# E03_DAQ.net
KiCad netlist of a schematic drawn in Altium Designer
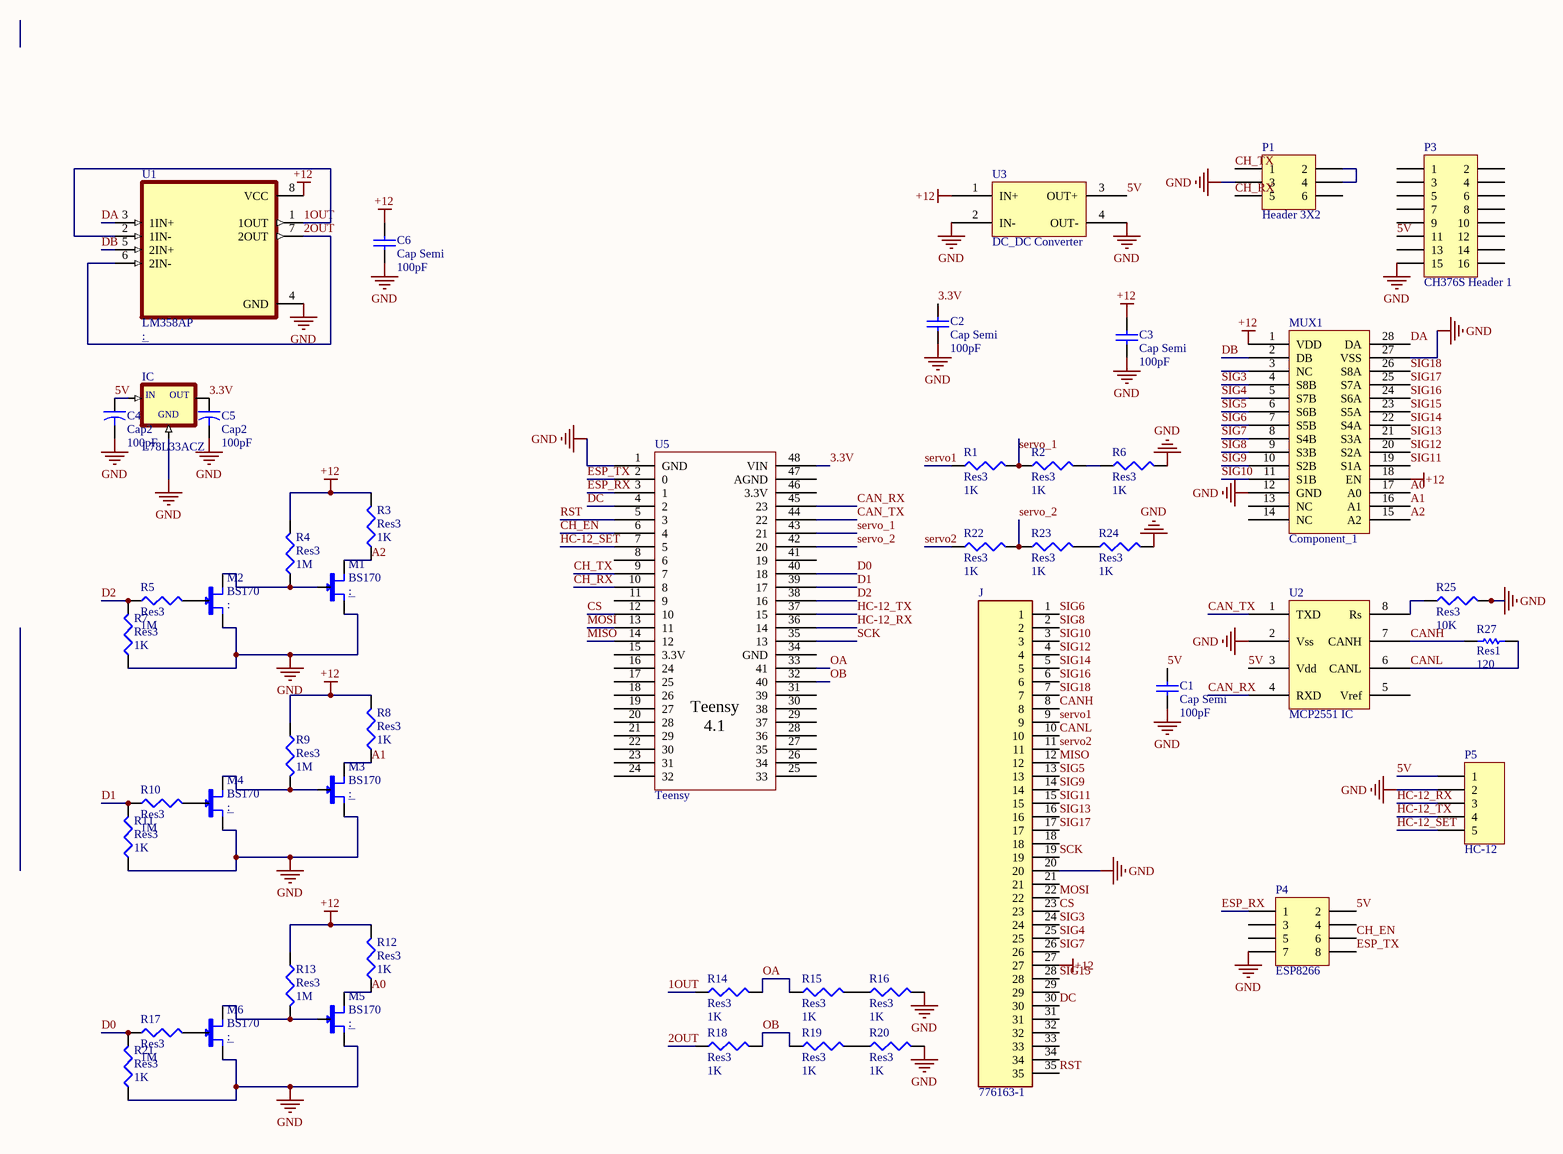
[diagram p0: E03_DAQ.SchDoc]

(export (version "E")
  (design (tool "Eeschema 10.0.6"))
  (components
    (comp (ref "C1")
      (value "Cap Semi")
      (footprint "C1210")
      (description "Capacitor (Semiconductor SIM Model)")
      (fields (field (name "ALTIUM_VALUE") "100pF") (field (name "PUBLISHER") "Altium Limited"))
      (libsource (lib "Miscellaneous Devices") (part "Cap Semi"))
    )
    (comp (ref "C2")
      (value "Cap Semi")
      (footprint "C1210")
      (description "Capacitor (Semiconductor SIM Model)")
      (fields (field (name "ALTIUM_VALUE") "100pF") (field (name "PUBLISHER") "Altium Limited"))
      (libsource (lib "Miscellaneous Devices") (part "Cap Semi"))
    )
    (comp (ref "C3")
      (value "Cap Semi")
      (footprint "C1210")
      (description "Capacitor (Semiconductor SIM Model)")
      (fields (field (name "ALTIUM_VALUE") "100pF") (field (name "PUBLISHER") "Altium Limited"))
      (libsource (lib "Miscellaneous Devices") (part "Cap Semi"))
    )
    (comp (ref "C4")
      (value "Cap2")
      (footprint "CAPR5-4X5")
      (description "Capacitor")
      (fields (field (name "ALTIUM_VALUE") "100pF") (field (name "PUBLISHER") "Altium Limited"))
      (libsource (lib "Miscellaneous Devices") (part "Cap2"))
    )
    (comp (ref "C5")
      (value "Cap2")
      (footprint "CAPR5-4X5")
      (description "Capacitor")
      (fields (field (name "ALTIUM_VALUE") "100pF") (field (name "PUBLISHER") "Altium Limited"))
      (libsource (lib "Miscellaneous Devices") (part "Cap2"))
    )
    (comp (ref "C6")
      (value "Cap Semi")
      (footprint "C1210")
      (description "Capacitor (Semiconductor SIM Model)")
      (fields (field (name "ALTIUM_VALUE") "100pF") (field (name "PUBLISHER") "Altium Limited"))
      (libsource (lib "Miscellaneous Devices") (part "Cap Semi"))
    )
    (comp (ref "IC")
      (value "L78L33ACZ")
      (footprint "TO92")
      (description "Linear Voltage Regulator IC 1 Output 100mA TO-92-3")
      (fields (field (name "MF") "STMicroelectronics"))
      (libsource (lib "L78L33ACZ") (part "L78L33ACZ"))
    )
    (comp (ref "J")
      (value "776163-1")
      (footprint "TE_776163-1")
      (description "Rectangular Power Connector, AMPSEAL Series, Through Hole, Plug, 35, 4 mm, Pin")
      (fields (field (name "DIGI-KEY_PART_NUMBER") "A106460-ND") (field (name "MF") "TE Connectivity"))
      (libsource (lib "776163-1") (part "776163-1"))
    )
    (comp (ref "M1")
      (value "BS170")
      (footprint "TRANSISTOR_TO-92")
      (description "N-Channel 60V 500mA (Ta) 830mW (Ta) Through Hole TO-92-3")
      (fields (field (name "MF") "ON Semiconductor"))
      (libsource (lib "BS170") (part "BS170"))
    )
    (comp (ref "M2")
      (value "BS170")
      (footprint "TRANSISTOR_TO-92")
      (description "N-Channel 60V 500mA (Ta) 830mW (Ta) Through Hole TO-92-3")
      (fields (field (name "MF") "ON Semiconductor"))
      (libsource (lib "BS170") (part "BS170"))
    )
    (comp (ref "M3")
      (value "BS170")
      (footprint "TRANSISTOR_TO-92")
      (description "N-Channel 60V 500mA (Ta) 830mW (Ta) Through Hole TO-92-3")
      (fields (field (name "MF") "ON Semiconductor"))
      (libsource (lib "BS170") (part "BS170"))
    )
    (comp (ref "M4")
      (value "BS170")
      (footprint "TRANSISTOR_TO-92")
      (description "N-Channel 60V 500mA (Ta) 830mW (Ta) Through Hole TO-92-3")
      (fields (field (name "MF") "ON Semiconductor"))
      (libsource (lib "BS170") (part "BS170"))
    )
    (comp (ref "M5")
      (value "BS170")
      (footprint "TRANSISTOR_TO-92")
      (description "N-Channel 60V 500mA (Ta) 830mW (Ta) Through Hole TO-92-3")
      (fields (field (name "MF") "ON Semiconductor"))
      (libsource (lib "BS170") (part "BS170"))
    )
    (comp (ref "M6")
      (value "BS170")
      (footprint "TRANSISTOR_TO-92")
      (description "N-Channel 60V 500mA (Ta) 830mW (Ta) Through Hole TO-92-3")
      (fields (field (name "MF") "ON Semiconductor"))
      (libsource (lib "BS170") (part "BS170"))
    )
    (comp (ref "MUX1")
      (value "Component_1")
      (footprint "*SOIC127P1030X265-28N")
      (libsource (lib "MUX") (part "Component_1"))
    )
    (comp (ref "P1")
      (value "Header 3X2")
      (footprint "HDR2X3")
      (description "Header, 3-Pin, Dual row")
      (fields (field (name "PUBLISHER") "Altium Limited"))
      (libsource (lib "Miscellaneous Connectors") (part "Header 3X2"))
    )
    (comp (ref "P3")
      (value "CH376S Header 1")
      (footprint "HDR2X8")
      (description "Header, 8-Pin, Dual row")
      (fields (field (name "PUBLISHER") "Altium Limited"))
      (libsource (lib "Miscellaneous Connectors") (part "Header 8X2"))
    )
    (comp (ref "P4")
      (value "ESP8266")
      (footprint "HDR2X4")
      (description "Header, 4-Pin, Dual row")
      (fields (field (name "PUBLISHER") "Altium Limited"))
      (libsource (lib "Miscellaneous Connectors") (part "Header 4X2"))
    )
    (comp (ref "P5")
      (value "HC-12")
      (footprint "HDR1X5")
      (description "Header, 5-Pin")
      (fields (field (name "PUBLISHER") "Altium Limited"))
      (libsource (lib "Miscellaneous Connectors") (part "Header 5"))
    )
    (comp (ref "R1")
      (value "Res3")
      (footprint "14-1210")
      (description "Resistor")
      (fields (field (name "ALTIUM_VALUE") "1K") (field (name "PUBLISHER") "Altium Limited"))
      (libsource (lib "Miscellaneous Devices") (part "Res3"))
    )
    (comp (ref "R2")
      (value "Res3")
      (footprint "14-1210")
      (description "Resistor")
      (fields (field (name "ALTIUM_VALUE") "1K") (field (name "PUBLISHER") "Altium Limited"))
      (libsource (lib "Miscellaneous Devices") (part "Res3"))
    )
    (comp (ref "R3")
      (value "Res3")
      (footprint "14-1210")
      (description "Resistor")
      (fields (field (name "ALTIUM_VALUE") "1K") (field (name "PUBLISHER") "Altium Limited"))
      (libsource (lib "Miscellaneous Devices") (part "Res3"))
    )
    (comp (ref "R4")
      (value "Res3")
      (footprint "14-1210")
      (description "Resistor")
      (fields (field (name "ALTIUM_VALUE") "1M") (field (name "PUBLISHER") "Altium Limited"))
      (libsource (lib "Miscellaneous Devices") (part "Res3"))
    )
    (comp (ref "R5")
      (value "Res3")
      (footprint "14-1210")
      (description "Resistor")
      (fields (field (name "ALTIUM_VALUE") "1M") (field (name "PUBLISHER") "Altium Limited"))
      (libsource (lib "Miscellaneous Devices") (part "Res3"))
    )
    (comp (ref "R6")
      (value "Res3")
      (footprint "14-1210")
      (description "Resistor")
      (fields (field (name "ALTIUM_VALUE") "1K") (field (name "PUBLISHER") "Altium Limited"))
      (libsource (lib "Miscellaneous Devices") (part "Res3"))
    )
    (comp (ref "R7")
      (value "Res3")
      (footprint "14-1210")
      (description "Resistor")
      (fields (field (name "ALTIUM_VALUE") "1K") (field (name "PUBLISHER") "Altium Limited"))
      (libsource (lib "Miscellaneous Devices") (part "Res3"))
    )
    (comp (ref "R8")
      (value "Res3")
      (footprint "14-1210")
      (description "Resistor")
      (fields (field (name "ALTIUM_VALUE") "1K") (field (name "PUBLISHER") "Altium Limited"))
      (libsource (lib "Miscellaneous Devices") (part "Res3"))
    )
    (comp (ref "R9")
      (value "Res3")
      (footprint "14-1210")
      (description "Resistor")
      (fields (field (name "ALTIUM_VALUE") "1M") (field (name "PUBLISHER") "Altium Limited"))
      (libsource (lib "Miscellaneous Devices") (part "Res3"))
    )
    (comp (ref "R10")
      (value "Res3")
      (footprint "14-1210")
      (description "Resistor")
      (fields (field (name "ALTIUM_VALUE") "1M") (field (name "PUBLISHER") "Altium Limited"))
      (libsource (lib "Miscellaneous Devices") (part "Res3"))
    )
    (comp (ref "R11")
      (value "Res3")
      (footprint "14-1210")
      (description "Resistor")
      (fields (field (name "ALTIUM_VALUE") "1K") (field (name "PUBLISHER") "Altium Limited"))
      (libsource (lib "Miscellaneous Devices") (part "Res3"))
    )
    (comp (ref "R12")
      (value "Res3")
      (footprint "14-1210")
      (description "Resistor")
      (fields (field (name "ALTIUM_VALUE") "1K") (field (name "PUBLISHER") "Altium Limited"))
      (libsource (lib "Miscellaneous Devices") (part "Res3"))
    )
    (comp (ref "R13")
      (value "Res3")
      (footprint "14-1210")
      (description "Resistor")
      (fields (field (name "ALTIUM_VALUE") "1M") (field (name "PUBLISHER") "Altium Limited"))
      (libsource (lib "Miscellaneous Devices") (part "Res3"))
    )
    (comp (ref "R14")
      (value "Res3")
      (footprint "14-1210")
      (description "Resistor")
      (fields (field (name "ALTIUM_VALUE") "1K") (field (name "PUBLISHER") "Altium Limited"))
      (libsource (lib "Miscellaneous Devices") (part "Res3"))
    )
    (comp (ref "R15")
      (value "Res3")
      (footprint "14-1210")
      (description "Resistor")
      (fields (field (name "ALTIUM_VALUE") "1K") (field (name "PUBLISHER") "Altium Limited"))
      (libsource (lib "Miscellaneous Devices") (part "Res3"))
    )
    (comp (ref "R16")
      (value "Res3")
      (footprint "14-1210")
      (description "Resistor")
      (fields (field (name "ALTIUM_VALUE") "1K") (field (name "PUBLISHER") "Altium Limited"))
      (libsource (lib "Miscellaneous Devices") (part "Res3"))
    )
    (comp (ref "R17")
      (value "Res3")
      (footprint "14-1210")
      (description "Resistor")
      (fields (field (name "ALTIUM_VALUE") "1M") (field (name "PUBLISHER") "Altium Limited"))
      (libsource (lib "Miscellaneous Devices") (part "Res3"))
    )
    (comp (ref "R18")
      (value "Res3")
      (footprint "14-1210")
      (description "Resistor")
      (fields (field (name "ALTIUM_VALUE") "1K") (field (name "PUBLISHER") "Altium Limited"))
      (libsource (lib "Miscellaneous Devices") (part "Res3"))
    )
    (comp (ref "R19")
      (value "Res3")
      (footprint "14-1210")
      (description "Resistor")
      (fields (field (name "ALTIUM_VALUE") "1K") (field (name "PUBLISHER") "Altium Limited"))
      (libsource (lib "Miscellaneous Devices") (part "Res3"))
    )
    (comp (ref "R20")
      (value "Res3")
      (footprint "14-1210")
      (description "Resistor")
      (fields (field (name "ALTIUM_VALUE") "1K") (field (name "PUBLISHER") "Altium Limited"))
      (libsource (lib "Miscellaneous Devices") (part "Res3"))
    )
    (comp (ref "R21")
      (value "Res3")
      (footprint "14-1210")
      (description "Resistor")
      (fields (field (name "ALTIUM_VALUE") "1K") (field (name "PUBLISHER") "Altium Limited"))
      (libsource (lib "Miscellaneous Devices") (part "Res3"))
    )
    (comp (ref "R22")
      (value "Res3")
      (footprint "14-1210")
      (description "Resistor")
      (fields (field (name "ALTIUM_VALUE") "1K") (field (name "PUBLISHER") "Altium Limited"))
      (libsource (lib "Miscellaneous Devices") (part "Res3"))
    )
    (comp (ref "R23")
      (value "Res3")
      (footprint "14-1210")
      (description "Resistor")
      (fields (field (name "ALTIUM_VALUE") "1K") (field (name "PUBLISHER") "Altium Limited"))
      (libsource (lib "Miscellaneous Devices") (part "Res3"))
    )
    (comp (ref "R24")
      (value "Res3")
      (footprint "14-1210")
      (description "Resistor")
      (fields (field (name "ALTIUM_VALUE") "1K") (field (name "PUBLISHER") "Altium Limited"))
      (libsource (lib "Miscellaneous Devices") (part "Res3"))
    )
    (comp (ref "R25")
      (value "Res3")
      (footprint "14-1210")
      (description "Resistor")
      (fields (field (name "ALTIUM_VALUE") "10K") (field (name "PUBLISHER") "Altium Limited"))
      (libsource (lib "Miscellaneous Devices") (part "Res3"))
    )
    (comp (ref "R27")
      (value "Res1")
      (footprint "AXIAL-0.3")
      (description "Resistor")
      (fields (field (name "ALTIUM_VALUE") "120") (field (name "PUBLISHER") "Altium Limited"))
      (libsource (lib "Miscellaneous Devices") (part "Res1"))
    )
    (comp (ref "U1")
      (value "LM358AP")
      (footprint "DIP794W45P254L959H508Q8")
      (description "Dual improved offset, standard operational amplifier<br /> &nbsp; 8-PDIP 0 to 70")
      (fields (field (name "MF") "Texas Instruments"))
      (libsource (lib "LM358AP") (part "LM358AP"))
    )
    (comp (ref "U2")
      (value "MCP2551 IC")
      (footprint "PCBComponent_1")
      (libsource (lib "MCP2551") (part "MCP2551"))
    )
    (comp (ref "U3")
      (value "DC_DC Converter")
      (footprint "PCBComponent_1")
      (libsource (lib "BUCK CONVERTER") (part "LM2576"))
    )
    (comp (ref "U5")
      (value "Teensy")
      (footprint "PCBComponent_1")
      (libsource (lib "Teensy4.1") (part "Teensy 4.1"))
    )
  )
  (nets
    (net (code "1") (name "+12") (class "Default")
      (node (ref "C3") (pin "2") (pinfunction "2_2") (pintype "passive"))
      (node (ref "C6") (pin "2") (pinfunction "2_2") (pintype "passive"))
      (node (ref "J") (pin "27") (pinfunction "27_27") (pintype "passive"))
      (node (ref "MUX1") (pin "1") (pinfunction "VDD_1") (pintype "passive"))
      (node (ref "MUX1") (pin "18") (pinfunction "EN_18") (pintype "passive"))
      (node (ref "R12") (pin "2") (pinfunction "2_2") (pintype "passive"))
      (node (ref "R13") (pin "1") (pinfunction "1_1") (pintype "passive"))
      (node (ref "R3") (pin "2") (pinfunction "2_2") (pintype "passive"))
      (node (ref "R4") (pin "2") (pinfunction "2_2") (pintype "passive"))
      (node (ref "R8") (pin "2") (pinfunction "2_2") (pintype "passive"))
      (node (ref "R9") (pin "1") (pinfunction "1_1") (pintype "passive"))
      (node (ref "U1") (pin "8") (pinfunction "VCC_8") (pintype "power_in"))
      (node (ref "U3") (pin "1") (pinfunction "IN+_1") (pintype "passive"))
    )
    (net (code "2") (name "/1OUT") (class "Default")
      (node (ref "R14") (pin "1") (pinfunction "1_1") (pintype "passive"))
      (node (ref "U1") (pin "1") (pinfunction "1OUT_1") (pintype "output"))
      (node (ref "U1") (pin "2") (pinfunction "1IN-_2") (pintype "input"))
    )
    (net (code "3") (name "/2OUT") (class "Default")
      (node (ref "R18") (pin "1") (pinfunction "1_1") (pintype "passive"))
      (node (ref "U1") (pin "6") (pinfunction "2IN-_6") (pintype "input"))
      (node (ref "U1") (pin "7") (pinfunction "2OUT_7") (pintype "output"))
    )
    (net (code "4") (name "/3.3V") (class "Default")
      (node (ref "C2") (pin "2") (pinfunction "2_2") (pintype "passive"))
      (node (ref "C5") (pin "1") (pinfunction "1_1") (pintype "passive"))
      (node (ref "IC") (pin "1") (pinfunction "OUT_1") (pintype "passive"))
      (node (ref "U5") (pin "48") (pinfunction "VIN_48") (pintype "passive"))
    )
    (net (code "5") (name "/5V") (class "Default")
      (node (ref "C1") (pin "2") (pinfunction "2_2") (pintype "passive"))
      (node (ref "C4") (pin "1") (pinfunction "1_1") (pintype "passive"))
      (node (ref "IC") (pin "3") (pinfunction "IN_3") (pintype "input"))
      (node (ref "P3") (pin "11") (pinfunction "11_11") (pintype "passive"))
      (node (ref "P4") (pin "2") (pinfunction "2_2") (pintype "passive"))
      (node (ref "P5") (pin "1") (pinfunction "1_1") (pintype "passive"))
      (node (ref "U2") (pin "3") (pinfunction "Vdd_3") (pintype "passive"))
      (node (ref "U3") (pin "3") (pinfunction "OUT+_3") (pintype "passive"))
    )
    (net (code "6") (name "/A0") (class "Default")
      (node (ref "M5") (pin "P$3") (pinfunction "D_P$3") (pintype "passive"))
      (node (ref "MUX1") (pin "17") (pinfunction "A0_17") (pintype "passive"))
      (node (ref "R12") (pin "1") (pinfunction "1_1") (pintype "passive"))
    )
    (net (code "7") (name "/A1") (class "Default")
      (node (ref "M3") (pin "P$3") (pinfunction "D_P$3") (pintype "passive"))
      (node (ref "MUX1") (pin "16") (pinfunction "A1_16") (pintype "passive"))
      (node (ref "R8") (pin "1") (pinfunction "1_1") (pintype "passive"))
    )
    (net (code "8") (name "/A2") (class "Default")
      (node (ref "M1") (pin "P$3") (pinfunction "D_P$3") (pintype "passive"))
      (node (ref "MUX1") (pin "15") (pinfunction "A2_15") (pintype "passive"))
      (node (ref "R3") (pin "1") (pinfunction "1_1") (pintype "passive"))
    )
    (net (code "9") (name "/CANH") (class "Default")
      (node (ref "J") (pin "8") (pinfunction "8_8") (pintype "passive"))
      (node (ref "R27") (pin "2") (pinfunction "2_2") (pintype "passive"))
      (node (ref "U2") (pin "7") (pinfunction "CANH_7") (pintype "passive"))
    )
    (net (code "10") (name "/CANL") (class "Default")
      (node (ref "J") (pin "10") (pinfunction "10_10") (pintype "passive"))
      (node (ref "R27") (pin "1") (pinfunction "1_1") (pintype "passive"))
      (node (ref "U2") (pin "6") (pinfunction "CANL_6") (pintype "passive"))
    )
    (net (code "11") (name "/CAN_RX") (class "Default")
      (node (ref "U2") (pin "4") (pinfunction "RXD_4") (pintype "passive"))
      (node (ref "U5") (pin "45") (pinfunction "23_45") (pintype "passive"))
    )
    (net (code "12") (name "/CAN_TX") (class "Default")
      (node (ref "U2") (pin "1") (pinfunction "TXD_1") (pintype "passive"))
      (node (ref "U5") (pin "44") (pinfunction "22_44") (pintype "passive"))
    )
    (net (code "13") (name "/CH_EN") (class "Default")
      (node (ref "P4") (pin "6") (pinfunction "6_6") (pintype "passive"))
      (node (ref "U5") (pin "6") (pinfunction "4_6") (pintype "passive"))
    )
    (net (code "14") (name "/CH_RX") (class "Default")
      (node (ref "P1") (pin "5") (pinfunction "5_5") (pintype "passive"))
      (node (ref "U5") (pin "10") (pinfunction "8_10") (pintype "passive"))
    )
    (net (code "15") (name "/CH_TX") (class "Default")
      (node (ref "P1") (pin "1") (pinfunction "1_1") (pintype "passive"))
      (node (ref "U5") (pin "9") (pinfunction "7_9") (pintype "passive"))
    )
    (net (code "16") (name "/CS") (class "Default")
      (node (ref "J") (pin "23") (pinfunction "23_23") (pintype "passive"))
      (node (ref "U5") (pin "12") (pinfunction "10_12") (pintype "passive"))
    )
    (net (code "17") (name "/D0") (class "Default")
      (node (ref "R17") (pin "1") (pinfunction "1_1") (pintype "passive"))
      (node (ref "R21") (pin "2") (pinfunction "2_2") (pintype "passive"))
      (node (ref "U5") (pin "40") (pinfunction "18_40") (pintype "passive"))
    )
    (net (code "18") (name "/D1") (class "Default")
      (node (ref "R10") (pin "1") (pinfunction "1_1") (pintype "passive"))
      (node (ref "R11") (pin "2") (pinfunction "2_2") (pintype "passive"))
      (node (ref "U5") (pin "39") (pinfunction "17_39") (pintype "passive"))
    )
    (net (code "19") (name "/D2") (class "Default")
      (node (ref "R5") (pin "1") (pinfunction "1_1") (pintype "passive"))
      (node (ref "R7") (pin "2") (pinfunction "2_2") (pintype "passive"))
      (node (ref "U5") (pin "38") (pinfunction "16_38") (pintype "passive"))
    )
    (net (code "20") (name "/DA") (class "Default")
      (node (ref "MUX1") (pin "28") (pinfunction "DA_28") (pintype "passive"))
      (node (ref "U1") (pin "3") (pinfunction "1IN+_3") (pintype "input"))
    )
    (net (code "21") (name "/DB") (class "Default")
      (node (ref "MUX1") (pin "2") (pinfunction "DB_2") (pintype "passive"))
      (node (ref "U1") (pin "5") (pinfunction "2IN+_5") (pintype "input"))
    )
    (net (code "22") (name "/DC") (class "Default")
      (node (ref "J") (pin "30") (pinfunction "30_30") (pintype "passive"))
      (node (ref "U5") (pin "4") (pinfunction "2_4") (pintype "passive"))
    )
    (net (code "23") (name "/ESP_RX") (class "Default")
      (node (ref "P4") (pin "1") (pinfunction "1_1") (pintype "passive"))
      (node (ref "U5") (pin "3") (pinfunction "1_3") (pintype "passive"))
    )
    (net (code "24") (name "/ESP_TX") (class "Default")
      (node (ref "P4") (pin "8") (pinfunction "8_8") (pintype "passive"))
      (node (ref "U5") (pin "2") (pinfunction "0_2") (pintype "passive"))
    )
    (net (code "25") (name "/HC-12_RX") (class "Default")
      (node (ref "P5") (pin "3") (pinfunction "3_3") (pintype "passive"))
      (node (ref "U5") (pin "36") (pinfunction "14_36") (pintype "passive"))
    )
    (net (code "26") (name "/HC-12_SET") (class "Default")
      (node (ref "P5") (pin "5") (pinfunction "5_5") (pintype "passive"))
      (node (ref "U5") (pin "7") (pinfunction "5_7") (pintype "passive"))
    )
    (net (code "27") (name "/HC-12_TX") (class "Default")
      (node (ref "P5") (pin "4") (pinfunction "4_4") (pintype "passive"))
      (node (ref "U5") (pin "37") (pinfunction "15_37") (pintype "passive"))
    )
    (net (code "28") (name "/MISO") (class "Default")
      (node (ref "J") (pin "12") (pinfunction "12_12") (pintype "passive"))
      (node (ref "U5") (pin "14") (pinfunction "12_14") (pintype "passive"))
    )
    (net (code "29") (name "/MOSI") (class "Default")
      (node (ref "J") (pin "22") (pinfunction "22_22") (pintype "passive"))
      (node (ref "U5") (pin "13") (pinfunction "11_13") (pintype "passive"))
    )
    (net (code "30") (name "/OA") (class "Default")
      (node (ref "R14") (pin "2") (pinfunction "2_2") (pintype "passive"))
      (node (ref "R15") (pin "1") (pinfunction "1_1") (pintype "passive"))
      (node (ref "U5") (pin "33") (pinfunction "41_33") (pintype "passive"))
    )
    (net (code "31") (name "/OB") (class "Default")
      (node (ref "R18") (pin "2") (pinfunction "2_2") (pintype "passive"))
      (node (ref "R19") (pin "1") (pinfunction "1_1") (pintype "passive"))
      (node (ref "U5") (pin "32") (pinfunction "40_32") (pintype "passive"))
    )
    (net (code "32") (name "/RST") (class "Default")
      (node (ref "J") (pin "35") (pinfunction "35_35") (pintype "passive"))
      (node (ref "U5") (pin "5") (pinfunction "3_5") (pintype "passive"))
    )
    (net (code "33") (name "/SCK") (class "Default")
      (node (ref "J") (pin "19") (pinfunction "19_19") (pintype "passive"))
      (node (ref "U5") (pin "35") (pinfunction "13_35") (pintype "passive"))
    )
    (net (code "34") (name "/SIG3") (class "Default")
      (node (ref "J") (pin "24") (pinfunction "24_24") (pintype "passive"))
      (node (ref "MUX1") (pin "4") (pinfunction "S8B_4") (pintype "passive"))
    )
    (net (code "35") (name "/SIG4") (class "Default")
      (node (ref "J") (pin "25") (pinfunction "25_25") (pintype "passive"))
      (node (ref "MUX1") (pin "5") (pinfunction "S7B_5") (pintype "passive"))
    )
    (net (code "36") (name "/SIG5") (class "Default")
      (node (ref "J") (pin "13") (pinfunction "13_13") (pintype "passive"))
      (node (ref "MUX1") (pin "6") (pinfunction "S6B_6") (pintype "passive"))
    )
    (net (code "37") (name "/SIG6") (class "Default")
      (node (ref "J") (pin "1") (pinfunction "1_1") (pintype "passive"))
      (node (ref "MUX1") (pin "7") (pinfunction "S5B_7") (pintype "passive"))
    )
    (net (code "38") (name "/SIG7") (class "Default")
      (node (ref "J") (pin "26") (pinfunction "26_26") (pintype "passive"))
      (node (ref "MUX1") (pin "8") (pinfunction "S4B_8") (pintype "passive"))
    )
    (net (code "39") (name "/SIG8") (class "Default")
      (node (ref "J") (pin "2") (pinfunction "2_2") (pintype "passive"))
      (node (ref "MUX1") (pin "9") (pinfunction "S3B_9") (pintype "passive"))
    )
    (net (code "40") (name "/SIG9") (class "Default")
      (node (ref "J") (pin "14") (pinfunction "14_14") (pintype "passive"))
      (node (ref "MUX1") (pin "10") (pinfunction "S2B_10") (pintype "passive"))
    )
    (net (code "41") (name "/SIG10") (class "Default")
      (node (ref "J") (pin "3") (pinfunction "3_3") (pintype "passive"))
      (node (ref "MUX1") (pin "11") (pinfunction "S1B_11") (pintype "passive"))
    )
    (net (code "42") (name "/SIG11") (class "Default")
      (node (ref "J") (pin "15") (pinfunction "15_15") (pintype "passive"))
      (node (ref "MUX1") (pin "19") (pinfunction "S1A_19") (pintype "passive"))
    )
    (net (code "43") (name "/SIG12") (class "Default")
      (node (ref "J") (pin "4") (pinfunction "4_4") (pintype "passive"))
      (node (ref "MUX1") (pin "20") (pinfunction "S2A_20") (pintype "passive"))
    )
    (net (code "44") (name "/SIG13") (class "Default")
      (node (ref "J") (pin "16") (pinfunction "16_16") (pintype "passive"))
      (node (ref "MUX1") (pin "21") (pinfunction "S3A_21") (pintype "passive"))
    )
    (net (code "45") (name "/SIG14") (class "Default")
      (node (ref "J") (pin "5") (pinfunction "5_5") (pintype "passive"))
      (node (ref "MUX1") (pin "22") (pinfunction "S4A_22") (pintype "passive"))
    )
    (net (code "46") (name "/SIG15") (class "Default")
      (node (ref "J") (pin "28") (pinfunction "28_28") (pintype "passive"))
      (node (ref "MUX1") (pin "23") (pinfunction "S5A_23") (pintype "passive"))
    )
    (net (code "47") (name "/SIG16") (class "Default")
      (node (ref "J") (pin "6") (pinfunction "6_6") (pintype "passive"))
      (node (ref "MUX1") (pin "24") (pinfunction "S6A_24") (pintype "passive"))
    )
    (net (code "48") (name "/SIG17") (class "Default")
      (node (ref "J") (pin "17") (pinfunction "17_17") (pintype "passive"))
      (node (ref "MUX1") (pin "25") (pinfunction "S7A_25") (pintype "passive"))
    )
    (net (code "49") (name "/SIG18") (class "Default")
      (node (ref "J") (pin "7") (pinfunction "7_7") (pintype "passive"))
      (node (ref "MUX1") (pin "26") (pinfunction "S8A_26") (pintype "passive"))
    )
    (net (code "50") (name "/servo1") (class "Default")
      (node (ref "J") (pin "9") (pinfunction "9_9") (pintype "passive"))
      (node (ref "R1") (pin "1") (pinfunction "1_1") (pintype "passive"))
    )
    (net (code "51") (name "/servo2") (class "Default")
      (node (ref "J") (pin "11") (pinfunction "11_11") (pintype "passive"))
      (node (ref "R22") (pin "1") (pinfunction "1_1") (pintype "passive"))
    )
    (net (code "52") (name "/servo_1") (class "Default")
      (node (ref "R1") (pin "2") (pinfunction "2_2") (pintype "passive"))
      (node (ref "R2") (pin "1") (pinfunction "1_1") (pintype "passive"))
      (node (ref "U5") (pin "43") (pinfunction "21_43") (pintype "passive"))
    )
    (net (code "53") (name "/servo_2") (class "Default")
      (node (ref "R22") (pin "2") (pinfunction "2_2") (pintype "passive"))
      (node (ref "R23") (pin "1") (pinfunction "1_1") (pintype "passive"))
      (node (ref "U5") (pin "42") (pinfunction "20_42") (pintype "passive"))
    )
    (net (code "54") (name "GND") (class "Default")
      (node (ref "C1") (pin "1") (pinfunction "1_1") (pintype "passive"))
      (node (ref "C2") (pin "1") (pinfunction "1_1") (pintype "passive"))
      (node (ref "C3") (pin "1") (pinfunction "1_1") (pintype "passive"))
      (node (ref "C4") (pin "2") (pinfunction "2_2") (pintype "passive"))
      (node (ref "C5") (pin "2") (pinfunction "2_2") (pintype "passive"))
      (node (ref "C6") (pin "1") (pinfunction "1_1") (pintype "passive"))
      (node (ref "IC") (pin "2") (pinfunction "GND_2") (pintype "input"))
      (node (ref "J") (pin "20") (pinfunction "20_20") (pintype "passive"))
      (node (ref "M1") (pin "P$1") (pinfunction "S_P$1") (pintype "passive"))
      (node (ref "M2") (pin "P$1") (pinfunction "S_P$1") (pintype "passive"))
      (node (ref "M3") (pin "P$1") (pinfunction "S_P$1") (pintype "passive"))
      (node (ref "M4") (pin "P$1") (pinfunction "S_P$1") (pintype "passive"))
      (node (ref "M5") (pin "P$1") (pinfunction "S_P$1") (pintype "passive"))
      (node (ref "M6") (pin "P$1") (pinfunction "S_P$1") (pintype "passive"))
      (node (ref "MUX1") (pin "12") (pinfunction "GND_12") (pintype "passive"))
      (node (ref "MUX1") (pin "27") (pinfunction "VSS_27") (pintype "passive"))
      (node (ref "P1") (pin "3") (pinfunction "3_3") (pintype "passive"))
      (node (ref "P3") (pin "15") (pinfunction "15_15") (pintype "passive"))
      (node (ref "P4") (pin "7") (pinfunction "7_7") (pintype "passive"))
      (node (ref "P5") (pin "2") (pinfunction "2_2") (pintype "passive"))
      (node (ref "R11") (pin "1") (pinfunction "1_1") (pintype "passive"))
      (node (ref "R16") (pin "2") (pinfunction "2_2") (pintype "passive"))
      (node (ref "R20") (pin "2") (pinfunction "2_2") (pintype "passive"))
      (node (ref "R21") (pin "1") (pinfunction "1_1") (pintype "passive"))
      (node (ref "R24") (pin "2") (pinfunction "2_2") (pintype "passive"))
      (node (ref "R25") (pin "2") (pinfunction "2_2") (pintype "passive"))
      (node (ref "R6") (pin "2") (pinfunction "2_2") (pintype "passive"))
      (node (ref "R7") (pin "1") (pinfunction "1_1") (pintype "passive"))
      (node (ref "U1") (pin "4") (pinfunction "GND_4") (pintype "power_in"))
      (node (ref "U2") (pin "2") (pinfunction "Vss_2") (pintype "passive"))
      (node (ref "U3") (pin "2") (pinfunction "IN-_2") (pintype "passive"))
      (node (ref "U3") (pin "4") (pinfunction "OUT-_4") (pintype "passive"))
      (node (ref "U5") (pin "1") (pinfunction "GND_1") (pintype "passive"))
    )
    (net (code "55") (name "Net-(M1-G)") (class "Default")
      (node (ref "M1") (pin "P$2") (pinfunction "G_P$2") (pintype "passive"))
      (node (ref "M2") (pin "P$3") (pinfunction "D_P$3") (pintype "passive"))
      (node (ref "R4") (pin "1") (pinfunction "1_1") (pintype "passive"))
    )
    (net (code "56") (name "Net-(M2-G)") (class "Default")
      (node (ref "M2") (pin "P$2") (pinfunction "G_P$2") (pintype "passive"))
      (node (ref "R5") (pin "2") (pinfunction "2_2") (pintype "passive"))
    )
    (net (code "57") (name "Net-(M3-G)") (class "Default")
      (node (ref "M3") (pin "P$2") (pinfunction "G_P$2") (pintype "passive"))
      (node (ref "M4") (pin "P$3") (pinfunction "D_P$3") (pintype "passive"))
      (node (ref "R9") (pin "2") (pinfunction "2_2") (pintype "passive"))
    )
    (net (code "58") (name "Net-(M4-G)") (class "Default")
      (node (ref "M4") (pin "P$2") (pinfunction "G_P$2") (pintype "passive"))
      (node (ref "R10") (pin "2") (pinfunction "2_2") (pintype "passive"))
    )
    (net (code "59") (name "Net-(M5-G)") (class "Default")
      (node (ref "M5") (pin "P$2") (pinfunction "G_P$2") (pintype "passive"))
      (node (ref "M6") (pin "P$3") (pinfunction "D_P$3") (pintype "passive"))
      (node (ref "R13") (pin "2") (pinfunction "2_2") (pintype "passive"))
    )
    (net (code "60") (name "Net-(M6-G)") (class "Default")
      (node (ref "M6") (pin "P$2") (pinfunction "G_P$2") (pintype "passive"))
      (node (ref "R17") (pin "2") (pinfunction "2_2") (pintype "passive"))
    )
    (net (code "61") (name "Net-(P1-Pad2)") (class "Default")
      (node (ref "P1") (pin "2") (pinfunction "2_2") (pintype "passive"))
      (node (ref "P1") (pin "4") (pinfunction "4_4") (pintype "passive"))
    )
    (net (code "62") (name "Net-(R2-Pad2)") (class "Default")
      (node (ref "R2") (pin "2") (pinfunction "2_2") (pintype "passive"))
      (node (ref "R6") (pin "1") (pinfunction "1_1") (pintype "passive"))
    )
    (net (code "63") (name "Net-(R15-Pad2)") (class "Default")
      (node (ref "R15") (pin "2") (pinfunction "2_2") (pintype "passive"))
      (node (ref "R16") (pin "1") (pinfunction "1_1") (pintype "passive"))
    )
    (net (code "64") (name "Net-(R19-Pad2)") (class "Default")
      (node (ref "R19") (pin "2") (pinfunction "2_2") (pintype "passive"))
      (node (ref "R20") (pin "1") (pinfunction "1_1") (pintype "passive"))
    )
    (net (code "65") (name "Net-(R23-Pad2)") (class "Default")
      (node (ref "R23") (pin "2") (pinfunction "2_2") (pintype "passive"))
      (node (ref "R24") (pin "1") (pinfunction "1_1") (pintype "passive"))
    )
    (net (code "66") (name "Net-(U2-Rs)") (class "Default")
      (node (ref "R25") (pin "1") (pinfunction "1_1") (pintype "passive"))
      (node (ref "U2") (pin "8") (pinfunction "Rs_8") (pintype "passive"))
    )
    (net (code "67") (name "unconnected-(J-Pad18)") (class "Default")
      (node (ref "J") (pin "18") (pinfunction "18_18") (pintype "passive"))
    )
    (net (code "68") (name "unconnected-(J-Pad21)") (class "Default")
      (node (ref "J") (pin "21") (pinfunction "21_21") (pintype "passive"))
    )
    (net (code "69") (name "unconnected-(J-Pad29)") (class "Default")
      (node (ref "J") (pin "29") (pinfunction "29_29") (pintype "passive"))
    )
    (net (code "70") (name "unconnected-(J-Pad31)") (class "Default")
      (node (ref "J") (pin "31") (pinfunction "31_31") (pintype "passive"))
    )
    (net (code "71") (name "unconnected-(J-Pad32)") (class "Default")
      (node (ref "J") (pin "32") (pinfunction "32_32") (pintype "passive"))
    )
    (net (code "72") (name "unconnected-(J-Pad33)") (class "Default")
      (node (ref "J") (pin "33") (pinfunction "33_33") (pintype "passive"))
    )
    (net (code "73") (name "unconnected-(J-Pad34)") (class "Default")
      (node (ref "J") (pin "34") (pinfunction "34_34") (pintype "passive"))
    )
    (net (code "74") (name "unconnected-(MUX1-NC-Pad3)") (class "Default")
      (node (ref "MUX1") (pin "3") (pinfunction "NC_3") (pintype "passive"))
    )
    (net (code "75") (name "unconnected-(MUX1-NC-Pad13)") (class "Default")
      (node (ref "MUX1") (pin "13") (pinfunction "NC_13") (pintype "passive"))
    )
    (net (code "76") (name "unconnected-(MUX1-NC-Pad14)") (class "Default")
      (node (ref "MUX1") (pin "14") (pinfunction "NC_14") (pintype "passive"))
    )
    (net (code "77") (name "unconnected-(P1-Pad6)") (class "Default")
      (node (ref "P1") (pin "6") (pinfunction "6_6") (pintype "passive"))
    )
    (net (code "78") (name "unconnected-(P3-Pad1)") (class "Default")
      (node (ref "P3") (pin "1") (pinfunction "1_1") (pintype "passive"))
    )
    (net (code "79") (name "unconnected-(P3-Pad2)") (class "Default")
      (node (ref "P3") (pin "2") (pinfunction "2_2") (pintype "passive"))
    )
    (net (code "80") (name "unconnected-(P3-Pad3)") (class "Default")
      (node (ref "P3") (pin "3") (pinfunction "3_3") (pintype "passive"))
    )
    (net (code "81") (name "unconnected-(P3-Pad4)") (class "Default")
      (node (ref "P3") (pin "4") (pinfunction "4_4") (pintype "passive"))
    )
    (net (code "82") (name "unconnected-(P3-Pad5)") (class "Default")
      (node (ref "P3") (pin "5") (pinfunction "5_5") (pintype "passive"))
    )
    (net (code "83") (name "unconnected-(P3-Pad6)") (class "Default")
      (node (ref "P3") (pin "6") (pinfunction "6_6") (pintype "passive"))
    )
    (net (code "84") (name "unconnected-(P3-Pad7)") (class "Default")
      (node (ref "P3") (pin "7") (pinfunction "7_7") (pintype "passive"))
    )
    (net (code "85") (name "unconnected-(P3-Pad8)") (class "Default")
      (node (ref "P3") (pin "8") (pinfunction "8_8") (pintype "passive"))
    )
    (net (code "86") (name "unconnected-(P3-Pad9)") (class "Default")
      (node (ref "P3") (pin "9") (pinfunction "9_9") (pintype "passive"))
    )
    (net (code "87") (name "unconnected-(P3-Pad10)") (class "Default")
      (node (ref "P3") (pin "10") (pinfunction "10_10") (pintype "passive"))
    )
    (net (code "88") (name "unconnected-(P3-Pad12)") (class "Default")
      (node (ref "P3") (pin "12") (pinfunction "12_12") (pintype "passive"))
    )
    (net (code "89") (name "unconnected-(P3-Pad13)") (class "Default")
      (node (ref "P3") (pin "13") (pinfunction "13_13") (pintype "passive"))
    )
    (net (code "90") (name "unconnected-(P3-Pad14)") (class "Default")
      (node (ref "P3") (pin "14") (pinfunction "14_14") (pintype "passive"))
    )
    (net (code "91") (name "unconnected-(P3-Pad16)") (class "Default")
      (node (ref "P3") (pin "16") (pinfunction "16_16") (pintype "passive"))
    )
    (net (code "92") (name "unconnected-(P4-Pad3)") (class "Default")
      (node (ref "P4") (pin "3") (pinfunction "3_3") (pintype "passive"))
    )
    (net (code "93") (name "unconnected-(P4-Pad4)") (class "Default")
      (node (ref "P4") (pin "4") (pinfunction "4_4") (pintype "passive"))
    )
    (net (code "94") (name "unconnected-(P4-Pad5)") (class "Default")
      (node (ref "P4") (pin "5") (pinfunction "5_5") (pintype "passive"))
    )
    (net (code "95") (name "unconnected-(U2-Vref-Pad5)") (class "Default")
      (node (ref "U2") (pin "5") (pinfunction "Vref_5") (pintype "passive"))
    )
    (net (code "96") (name "unconnected-(U5-3.3V-Pad15)") (class "Default")
      (node (ref "U5") (pin "15") (pinfunction "3.3V_15") (pintype "passive"))
    )
    (net (code "97") (name "unconnected-(U5-3.3V-Pad46)") (class "Default")
      (node (ref "U5") (pin "46") (pinfunction "3.3V_46") (pintype "passive"))
    )
    (net (code "98") (name "unconnected-(U5-6-Pad8)") (class "Default")
      (node (ref "U5") (pin "8") (pinfunction "6_8") (pintype "passive"))
    )
    (net (code "99") (name "unconnected-(U5-9-Pad11)") (class "Default")
      (node (ref "U5") (pin "11") (pinfunction "9_11") (pintype "passive"))
    )
    (net (code "100") (name "unconnected-(U5-19-Pad41)") (class "Default")
      (node (ref "U5") (pin "41") (pinfunction "19_41") (pintype "passive"))
    )
    (net (code "101") (name "unconnected-(U5-24-Pad16)") (class "Default")
      (node (ref "U5") (pin "16") (pinfunction "24_16") (pintype "passive"))
    )
    (net (code "102") (name "unconnected-(U5-25-Pad17)") (class "Default")
      (node (ref "U5") (pin "17") (pinfunction "25_17") (pintype "passive"))
    )
    (net (code "103") (name "unconnected-(U5-26-Pad18)") (class "Default")
      (node (ref "U5") (pin "18") (pinfunction "26_18") (pintype "passive"))
    )
    (net (code "104") (name "unconnected-(U5-27-Pad19)") (class "Default")
      (node (ref "U5") (pin "19") (pinfunction "27_19") (pintype "passive"))
    )
    (net (code "105") (name "unconnected-(U5-28-Pad20)") (class "Default")
      (node (ref "U5") (pin "20") (pinfunction "28_20") (pintype "passive"))
    )
    (net (code "106") (name "unconnected-(U5-29-Pad21)") (class "Default")
      (node (ref "U5") (pin "21") (pinfunction "29_21") (pintype "passive"))
    )
    (net (code "107") (name "unconnected-(U5-30-Pad22)") (class "Default")
      (node (ref "U5") (pin "22") (pinfunction "30_22") (pintype "passive"))
    )
    (net (code "108") (name "unconnected-(U5-31-Pad23)") (class "Default")
      (node (ref "U5") (pin "23") (pinfunction "31_23") (pintype "passive"))
    )
    (net (code "109") (name "unconnected-(U5-32-Pad24)") (class "Default")
      (node (ref "U5") (pin "24") (pinfunction "32_24") (pintype "passive"))
    )
    (net (code "110") (name "unconnected-(U5-33-Pad25)") (class "Default")
      (node (ref "U5") (pin "25") (pinfunction "33_25") (pintype "passive"))
    )
    (net (code "111") (name "unconnected-(U5-34-Pad26)") (class "Default")
      (node (ref "U5") (pin "26") (pinfunction "34_26") (pintype "passive"))
    )
    (net (code "112") (name "unconnected-(U5-35-Pad27)") (class "Default")
      (node (ref "U5") (pin "27") (pinfunction "35_27") (pintype "passive"))
    )
    (net (code "113") (name "unconnected-(U5-36-Pad28)") (class "Default")
      (node (ref "U5") (pin "28") (pinfunction "36_28") (pintype "passive"))
    )
    (net (code "114") (name "unconnected-(U5-37-Pad29)") (class "Default")
      (node (ref "U5") (pin "29") (pinfunction "37_29") (pintype "passive"))
    )
    (net (code "115") (name "unconnected-(U5-38-Pad30)") (class "Default")
      (node (ref "U5") (pin "30") (pinfunction "38_30") (pintype "passive"))
    )
    (net (code "116") (name "unconnected-(U5-39-Pad31)") (class "Default")
      (node (ref "U5") (pin "31") (pinfunction "39_31") (pintype "passive"))
    )
    (net (code "117") (name "unconnected-(U5-AGND-Pad47)") (class "Default")
      (node (ref "U5") (pin "47") (pinfunction "AGND_47") (pintype "passive"))
    )
    (net (code "118") (name "unconnected-(U5-GND-Pad34)") (class "Default")
      (node (ref "U5") (pin "34") (pinfunction "GND_34") (pintype "passive"))
    )
  )
)
